# mag_comp.net
KiCad netlist of a schematic drawn in EAGLE
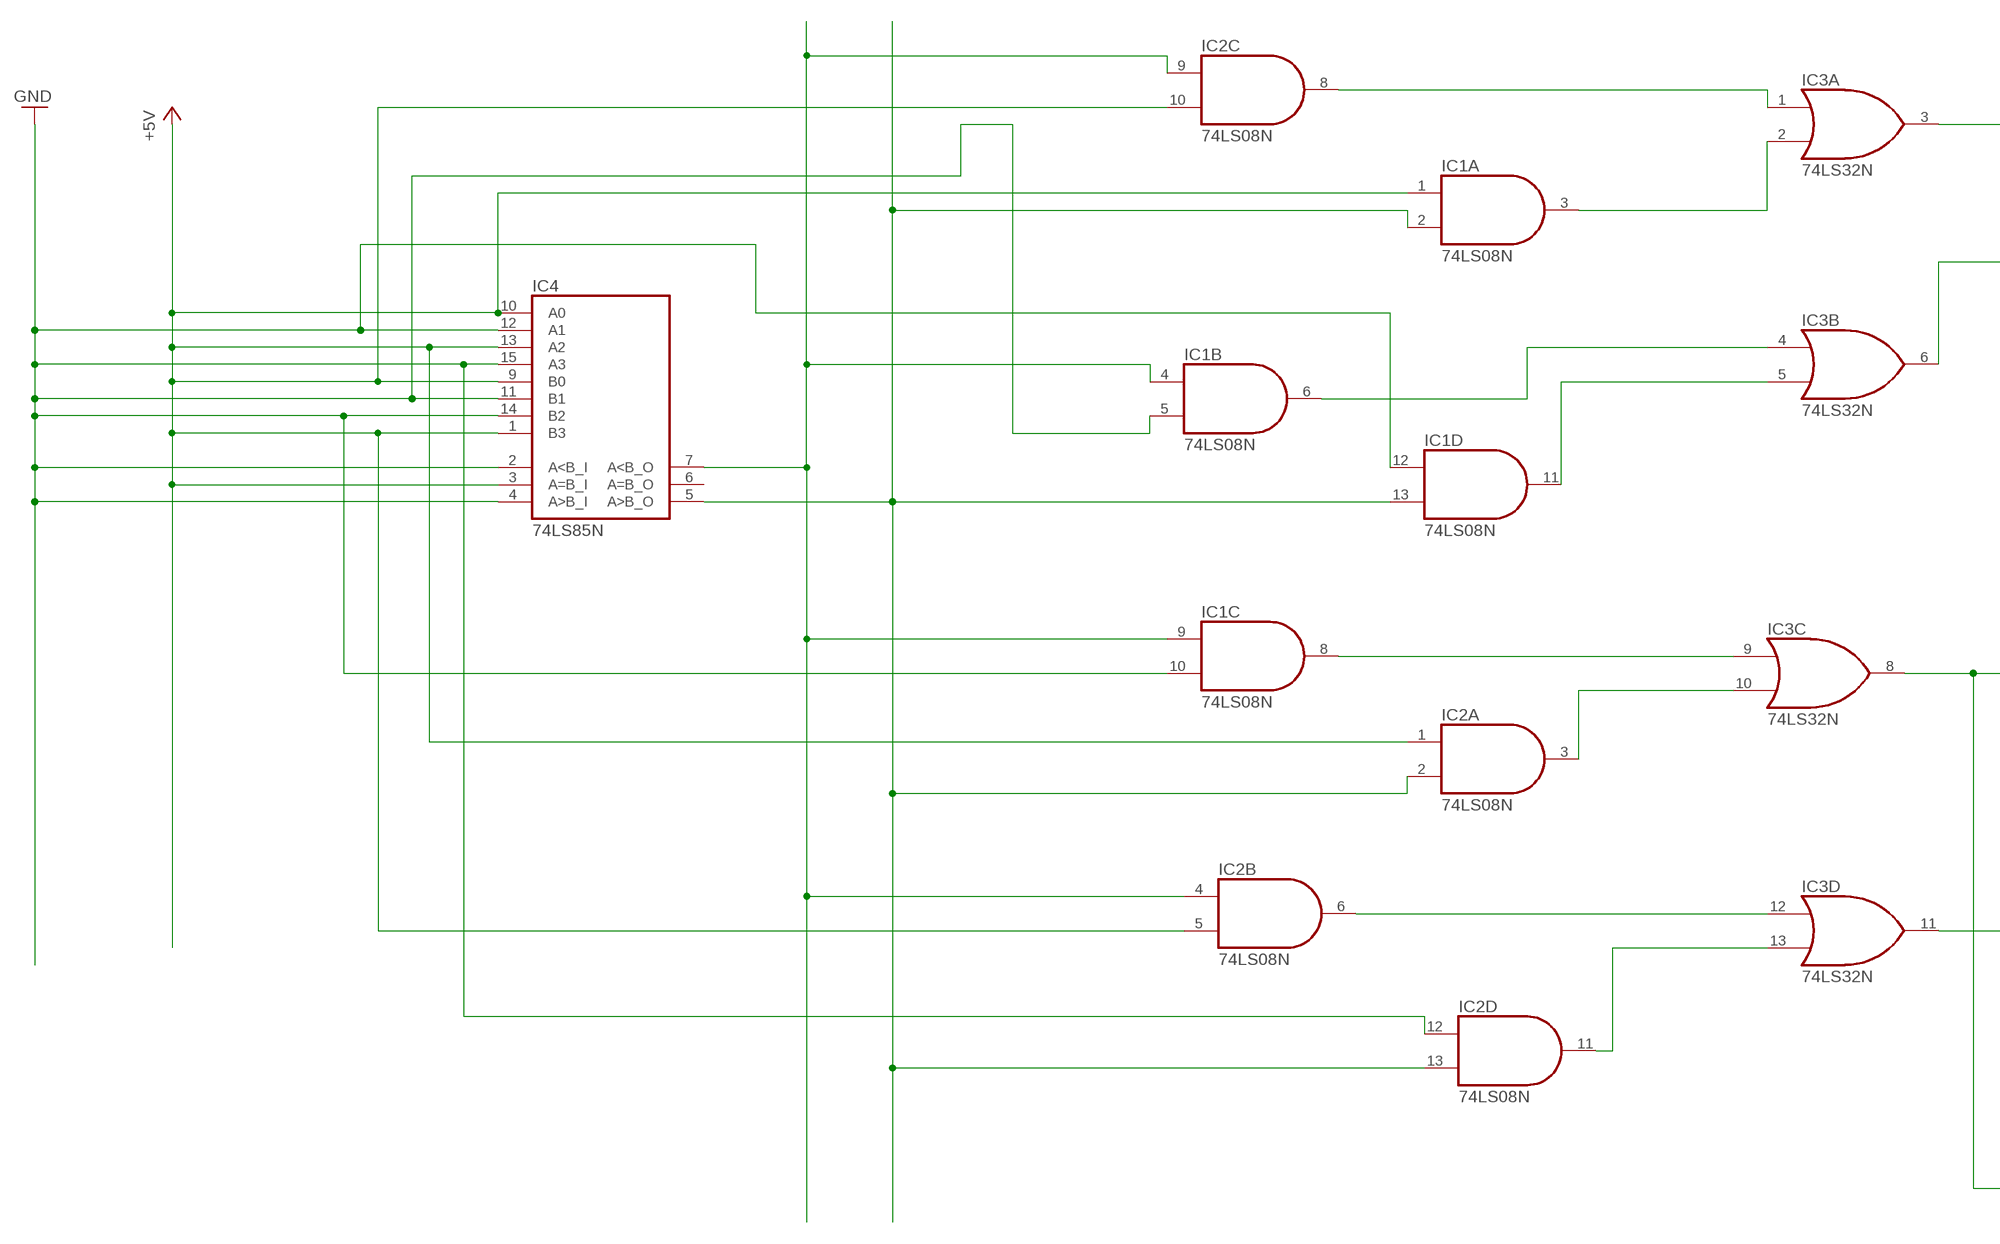
[diagram p0: schematic, sheet 1, part 1 of 2]
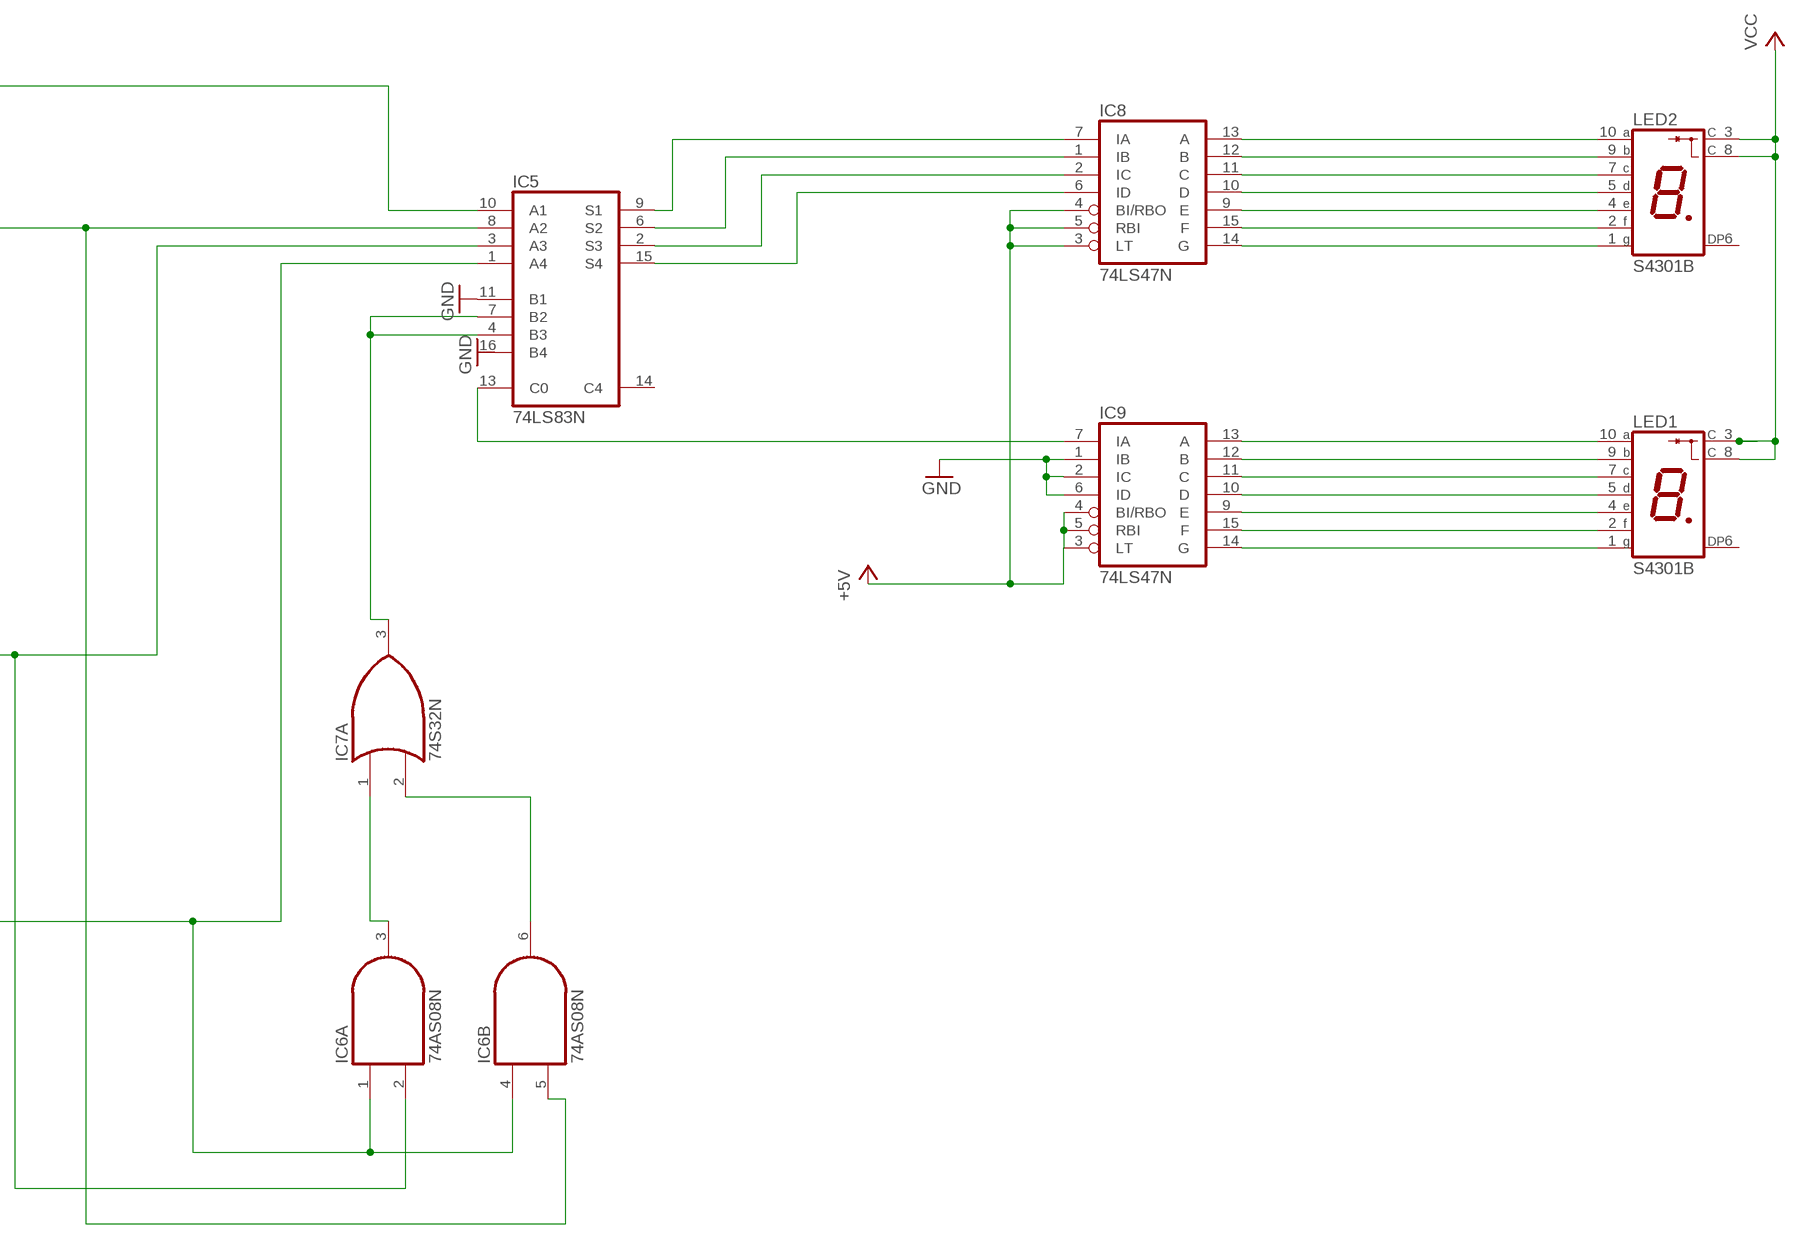
[diagram p1: schematic, sheet 1, part 2 of 2]

(export (version "E")
  (design (tool "Eeschema 10.0.6"))
  (components
    (comp (ref "IC1")
      (value "74LS08N")
      (footprint "eagle-import:DIL14")
      (libsource (lib "eagle-import") (part "7408NLS"))
    )
    (comp (ref "IC2")
      (value "74LS08N")
      (footprint "eagle-import:DIL14")
      (libsource (lib "eagle-import") (part "7408NLS"))
    )
    (comp (ref "IC3")
      (value "74LS32N")
      (footprint "eagle-import:DIL14")
      (libsource (lib "eagle-import") (part "7432NLS"))
    )
    (comp (ref "IC4")
      (value "74LS85N")
      (footprint "eagle-import:DIL16")
      (libsource (lib "eagle-import") (part "7485NLS"))
    )
    (comp (ref "IC5")
      (value "74LS83N")
      (footprint "eagle-import:DIL16")
      (libsource (lib "eagle-import") (part "7483NLS"))
    )
    (comp (ref "IC6")
      (value "74AS08N")
      (footprint "eagle-import:DIL14")
      (libsource (lib "eagle-import") (part "7408NAS"))
    )
    (comp (ref "IC7")
      (value "74S32N")
      (footprint "eagle-import:DIL14")
      (libsource (lib "eagle-import") (part "7432NS"))
    )
    (comp (ref "IC8")
      (value "74LS47N")
      (footprint "eagle-import:DIL16")
      (libsource (lib "eagle-import") (part "7447NLS"))
    )
    (comp (ref "IC9")
      (value "74LS47N")
      (footprint "eagle-import:DIL16")
      (libsource (lib "eagle-import") (part "7447NLS"))
    )
    (comp (ref "LED1")
      (value "S4301B")
      (footprint "eagle-import:S4301B")
      (libsource (lib "eagle-import") (part "S4301B"))
    )
    (comp (ref "LED2")
      (value "S4301B")
      (footprint "eagle-import:S4301B")
      (libsource (lib "eagle-import") (part "S4301B"))
    )
  )
  (nets
    (net (code "1") (name "+5V") (class "Default")
      (node (ref "IC1") (pin "1") (pinfunction "I0_1") (pintype "input"))
      (node (ref "IC2") (pin "1") (pinfunction "I0_1") (pintype "input"))
      (node (ref "IC2") (pin "10") (pinfunction "I1_10") (pintype "input"))
      (node (ref "IC2") (pin "5") (pinfunction "I1_5") (pintype "input"))
      (node (ref "IC4") (pin "1") (pinfunction "B3_1") (pintype "input"))
      (node (ref "IC4") (pin "10") (pinfunction "A0_10") (pintype "input"))
      (node (ref "IC4") (pin "13") (pinfunction "A2_13") (pintype "input"))
      (node (ref "IC4") (pin "3") (pinfunction "A=B_I_3") (pintype "input"))
      (node (ref "IC4") (pin "9") (pinfunction "B0_9") (pintype "input"))
      (node (ref "IC8") (pin "3") (pinfunction "LT_3") (pintype "input"))
      (node (ref "IC8") (pin "4") (pinfunction "BI/RBO_4") (pintype "input"))
      (node (ref "IC8") (pin "5") (pinfunction "RBI_5") (pintype "input"))
      (node (ref "IC9") (pin "3") (pinfunction "LT_3") (pintype "input"))
      (node (ref "IC9") (pin "4") (pinfunction "BI/RBO_4") (pintype "input"))
      (node (ref "IC9") (pin "5") (pinfunction "RBI_5") (pintype "input"))
    )
    (net (code "2") (name "GND") (class "Default")
      (node (ref "IC1") (pin "10") (pinfunction "I1_10") (pintype "input"))
      (node (ref "IC1") (pin "12") (pinfunction "I0_12") (pintype "input"))
      (node (ref "IC1") (pin "5") (pinfunction "I1_5") (pintype "input"))
      (node (ref "IC2") (pin "12") (pinfunction "I0_12") (pintype "input"))
      (node (ref "IC4") (pin "11") (pinfunction "B1_11") (pintype "input"))
      (node (ref "IC4") (pin "12") (pinfunction "A1_12") (pintype "input"))
      (node (ref "IC4") (pin "14") (pinfunction "B2_14") (pintype "input"))
      (node (ref "IC4") (pin "15") (pinfunction "A3_15") (pintype "input"))
      (node (ref "IC4") (pin "2") (pinfunction "A<B_I_2") (pintype "input"))
      (node (ref "IC4") (pin "4") (pinfunction "A>B_I_4") (pintype "input"))
      (node (ref "IC5") (pin "11") (pinfunction "B1_11") (pintype "input"))
      (node (ref "IC9") (pin "1") (pinfunction "IB_1") (pintype "input"))
      (node (ref "IC9") (pin "2") (pinfunction "IC_2") (pintype "input"))
      (node (ref "IC9") (pin "6") (pinfunction "ID_6") (pintype "input"))
    )
    (net (code "3") (name "Net-(IC1A-I1)") (class "Default")
      (node (ref "IC1") (pin "13") (pinfunction "I1_13") (pintype "input"))
      (node (ref "IC1") (pin "2") (pinfunction "I1_2") (pintype "input"))
      (node (ref "IC2") (pin "13") (pinfunction "I1_13") (pintype "input"))
      (node (ref "IC2") (pin "2") (pinfunction "I1_2") (pintype "input"))
      (node (ref "IC4") (pin "5") (pinfunction "A>B_O_5") (pintype "output"))
    )
    (net (code "4") (name "Net-(IC1A-O)") (class "Default")
      (node (ref "IC1") (pin "3") (pinfunction "O_3") (pintype "output"))
      (node (ref "IC3") (pin "2") (pinfunction "I1_2") (pintype "input"))
    )
    (net (code "5") (name "Net-(IC1B-I0)") (class "Default")
      (node (ref "IC1") (pin "4") (pinfunction "I0_4") (pintype "input"))
      (node (ref "IC1") (pin "9") (pinfunction "I0_9") (pintype "input"))
      (node (ref "IC2") (pin "4") (pinfunction "I0_4") (pintype "input"))
      (node (ref "IC2") (pin "9") (pinfunction "I0_9") (pintype "input"))
      (node (ref "IC4") (pin "7") (pinfunction "A<B_O_7") (pintype "output"))
    )
    (net (code "6") (name "Net-(IC1B-O)") (class "Default")
      (node (ref "IC1") (pin "6") (pinfunction "O_6") (pintype "output"))
      (node (ref "IC3") (pin "4") (pinfunction "I0_4") (pintype "input"))
    )
    (net (code "7") (name "Net-(IC1C-O)") (class "Default")
      (node (ref "IC1") (pin "8") (pinfunction "O_8") (pintype "output"))
      (node (ref "IC3") (pin "9") (pinfunction "I0_9") (pintype "input"))
    )
    (net (code "8") (name "Net-(IC1D-O)") (class "Default")
      (node (ref "IC1") (pin "11") (pinfunction "O_11") (pintype "output"))
      (node (ref "IC3") (pin "5") (pinfunction "I1_5") (pintype "input"))
    )
    (net (code "9") (name "Net-(IC2A-O)") (class "Default")
      (node (ref "IC2") (pin "3") (pinfunction "O_3") (pintype "output"))
      (node (ref "IC3") (pin "10") (pinfunction "I1_10") (pintype "input"))
    )
    (net (code "10") (name "Net-(IC2B-O)") (class "Default")
      (node (ref "IC2") (pin "6") (pinfunction "O_6") (pintype "output"))
      (node (ref "IC3") (pin "12") (pinfunction "I0_12") (pintype "input"))
    )
    (net (code "11") (name "Net-(IC2C-O)") (class "Default")
      (node (ref "IC2") (pin "8") (pinfunction "O_8") (pintype "output"))
      (node (ref "IC3") (pin "1") (pinfunction "I0_1") (pintype "input"))
    )
    (net (code "12") (name "Net-(IC2D-O)") (class "Default")
      (node (ref "IC2") (pin "11") (pinfunction "O_11") (pintype "output"))
      (node (ref "IC3") (pin "13") (pinfunction "I1_13") (pintype "input"))
    )
    (net (code "13") (name "Net-(IC3A-O)") (class "Default")
      (node (ref "IC3") (pin "3") (pinfunction "O_3") (pintype "output"))
      (node (ref "IC5") (pin "10") (pinfunction "A1_10") (pintype "input"))
    )
    (net (code "14") (name "Net-(IC3B-O)") (class "Default")
      (node (ref "IC3") (pin "6") (pinfunction "O_6") (pintype "output"))
      (node (ref "IC5") (pin "8") (pinfunction "A2_8") (pintype "input"))
      (node (ref "IC6") (pin "5") (pinfunction "I1_5") (pintype "input"))
    )
    (net (code "15") (name "Net-(IC3C-O)") (class "Default")
      (node (ref "IC3") (pin "8") (pinfunction "O_8") (pintype "output"))
      (node (ref "IC5") (pin "3") (pinfunction "A3_3") (pintype "input"))
      (node (ref "IC6") (pin "2") (pinfunction "I1_2") (pintype "input"))
    )
    (net (code "16") (name "Net-(IC3D-O)") (class "Default")
      (node (ref "IC3") (pin "11") (pinfunction "O_11") (pintype "output"))
      (node (ref "IC5") (pin "1") (pinfunction "A4_1") (pintype "input"))
      (node (ref "IC6") (pin "1") (pinfunction "I0_1") (pintype "input"))
      (node (ref "IC6") (pin "4") (pinfunction "I0_4") (pintype "input"))
    )
    (net (code "17") (name "Net-(IC5A-B2)") (class "Default")
      (node (ref "IC5") (pin "4") (pinfunction "B3_4") (pintype "input"))
      (node (ref "IC5") (pin "7") (pinfunction "B2_7") (pintype "input"))
      (node (ref "IC7") (pin "3") (pinfunction "O_3") (pintype "output"))
    )
    (net (code "18") (name "Net-(IC5A-C0)") (class "Default")
      (node (ref "IC5") (pin "13") (pinfunction "C0_13") (pintype "input"))
      (node (ref "IC9") (pin "7") (pinfunction "IA_7") (pintype "input"))
    )
    (net (code "19") (name "Net-(IC5A-S1)") (class "Default")
      (node (ref "IC5") (pin "9") (pinfunction "S1_9") (pintype "output"))
      (node (ref "IC8") (pin "7") (pinfunction "IA_7") (pintype "input"))
    )
    (net (code "20") (name "Net-(IC5A-S2)") (class "Default")
      (node (ref "IC5") (pin "6") (pinfunction "S2_6") (pintype "output"))
      (node (ref "IC8") (pin "1") (pinfunction "IB_1") (pintype "input"))
    )
    (net (code "21") (name "Net-(IC5A-S3)") (class "Default")
      (node (ref "IC5") (pin "2") (pinfunction "S3_2") (pintype "output"))
      (node (ref "IC8") (pin "2") (pinfunction "IC_2") (pintype "input"))
    )
    (net (code "22") (name "Net-(IC5A-S4)") (class "Default")
      (node (ref "IC5") (pin "15") (pinfunction "S4_15") (pintype "output"))
      (node (ref "IC8") (pin "6") (pinfunction "ID_6") (pintype "input"))
    )
    (net (code "23") (name "Net-(IC6A-O)") (class "Default")
      (node (ref "IC6") (pin "3") (pinfunction "O_3") (pintype "output"))
      (node (ref "IC7") (pin "1") (pinfunction "I0_1") (pintype "input"))
    )
    (net (code "24") (name "Net-(IC6B-O)") (class "Default")
      (node (ref "IC6") (pin "6") (pinfunction "O_6") (pintype "output"))
      (node (ref "IC7") (pin "2") (pinfunction "I1_2") (pintype "input"))
    )
    (net (code "25") (name "Net-(IC8A-A)") (class "Default")
      (node (ref "IC8") (pin "13") (pinfunction "A_13") (pintype "output"))
      (node (ref "LED2") (pin "10") (pinfunction "A_10") (pintype "passive"))
    )
    (net (code "26") (name "Net-(IC8A-B)") (class "Default")
      (node (ref "IC8") (pin "12") (pinfunction "B_12") (pintype "output"))
      (node (ref "LED2") (pin "9") (pinfunction "B_9") (pintype "passive"))
    )
    (net (code "27") (name "Net-(IC8A-C)") (class "Default")
      (node (ref "IC8") (pin "11") (pinfunction "C_11") (pintype "output"))
      (node (ref "LED2") (pin "7") (pinfunction "C_7") (pintype "passive"))
    )
    (net (code "28") (name "Net-(IC8A-D)") (class "Default")
      (node (ref "IC8") (pin "10") (pinfunction "D_10") (pintype "output"))
      (node (ref "LED2") (pin "5") (pinfunction "D_5") (pintype "passive"))
    )
    (net (code "29") (name "Net-(IC8A-E)") (class "Default")
      (node (ref "IC8") (pin "9") (pinfunction "E_9") (pintype "output"))
      (node (ref "LED2") (pin "4") (pinfunction "E_4") (pintype "passive"))
    )
    (net (code "30") (name "Net-(IC8A-F)") (class "Default")
      (node (ref "IC8") (pin "15") (pinfunction "F_15") (pintype "output"))
      (node (ref "LED2") (pin "2") (pinfunction "F_2") (pintype "passive"))
    )
    (net (code "31") (name "Net-(IC8A-G)") (class "Default")
      (node (ref "IC8") (pin "14") (pinfunction "G_14") (pintype "output"))
      (node (ref "LED2") (pin "1") (pinfunction "G_1") (pintype "passive"))
    )
    (net (code "32") (name "Net-(IC9A-A)") (class "Default")
      (node (ref "IC9") (pin "13") (pinfunction "A_13") (pintype "output"))
      (node (ref "LED1") (pin "10") (pinfunction "A_10") (pintype "passive"))
    )
    (net (code "33") (name "Net-(IC9A-B)") (class "Default")
      (node (ref "IC9") (pin "12") (pinfunction "B_12") (pintype "output"))
      (node (ref "LED1") (pin "9") (pinfunction "B_9") (pintype "passive"))
    )
    (net (code "34") (name "Net-(IC9A-C)") (class "Default")
      (node (ref "IC9") (pin "11") (pinfunction "C_11") (pintype "output"))
      (node (ref "LED1") (pin "7") (pinfunction "C_7") (pintype "passive"))
    )
    (net (code "35") (name "Net-(IC9A-D)") (class "Default")
      (node (ref "IC9") (pin "10") (pinfunction "D_10") (pintype "output"))
      (node (ref "LED1") (pin "5") (pinfunction "D_5") (pintype "passive"))
    )
    (net (code "36") (name "Net-(IC9A-E)") (class "Default")
      (node (ref "IC9") (pin "9") (pinfunction "E_9") (pintype "output"))
      (node (ref "LED1") (pin "4") (pinfunction "E_4") (pintype "passive"))
    )
    (net (code "37") (name "Net-(IC9A-F)") (class "Default")
      (node (ref "IC9") (pin "15") (pinfunction "F_15") (pintype "output"))
      (node (ref "LED1") (pin "2") (pinfunction "F_2") (pintype "passive"))
    )
    (net (code "38") (name "Net-(IC9A-G)") (class "Default")
      (node (ref "IC9") (pin "14") (pinfunction "G_14") (pintype "output"))
      (node (ref "LED1") (pin "1") (pinfunction "G_1") (pintype "passive"))
    )
    (net (code "39") (name "VCC") (class "Default")
      (node (ref "LED1") (pin "3") (pinfunction "C_3") (pintype "passive"))
      (node (ref "LED1") (pin "8") (pinfunction "C_8") (pintype "passive"))
      (node (ref "LED2") (pin "3") (pinfunction "C_3") (pintype "passive"))
      (node (ref "LED2") (pin "8") (pinfunction "C_8") (pintype "passive"))
    )
    (net (code "40") (name "unconnected-(IC4A-A=B_O-Pad6)") (class "Default")
      (node (ref "IC4") (pin "6") (pinfunction "A=B_O_6") (pintype "output"))
    )
    (net (code "41") (name "unconnected-(IC5A-B4-Pad16)") (class "Default")
      (node (ref "IC5") (pin "16") (pinfunction "B4_16") (pintype "input"))
    )
    (net (code "42") (name "unconnected-(IC5A-C4-Pad14)") (class "Default")
      (node (ref "IC5") (pin "14") (pinfunction "C4_14") (pintype "output"))
    )
    (net (code "43") (name "unconnected-(LED1-DP-Pad6)") (class "Default")
      (node (ref "LED1") (pin "6") (pinfunction "DP_6") (pintype "passive"))
    )
    (net (code "44") (name "unconnected-(LED2-DP-Pad6)") (class "Default")
      (node (ref "LED2") (pin "6") (pinfunction "DP_6") (pintype "passive"))
    )
  )
)
